# LEDBatterychargeIndicatorCircuitV2.net
KiCad netlist of a schematic drawn in EAGLE
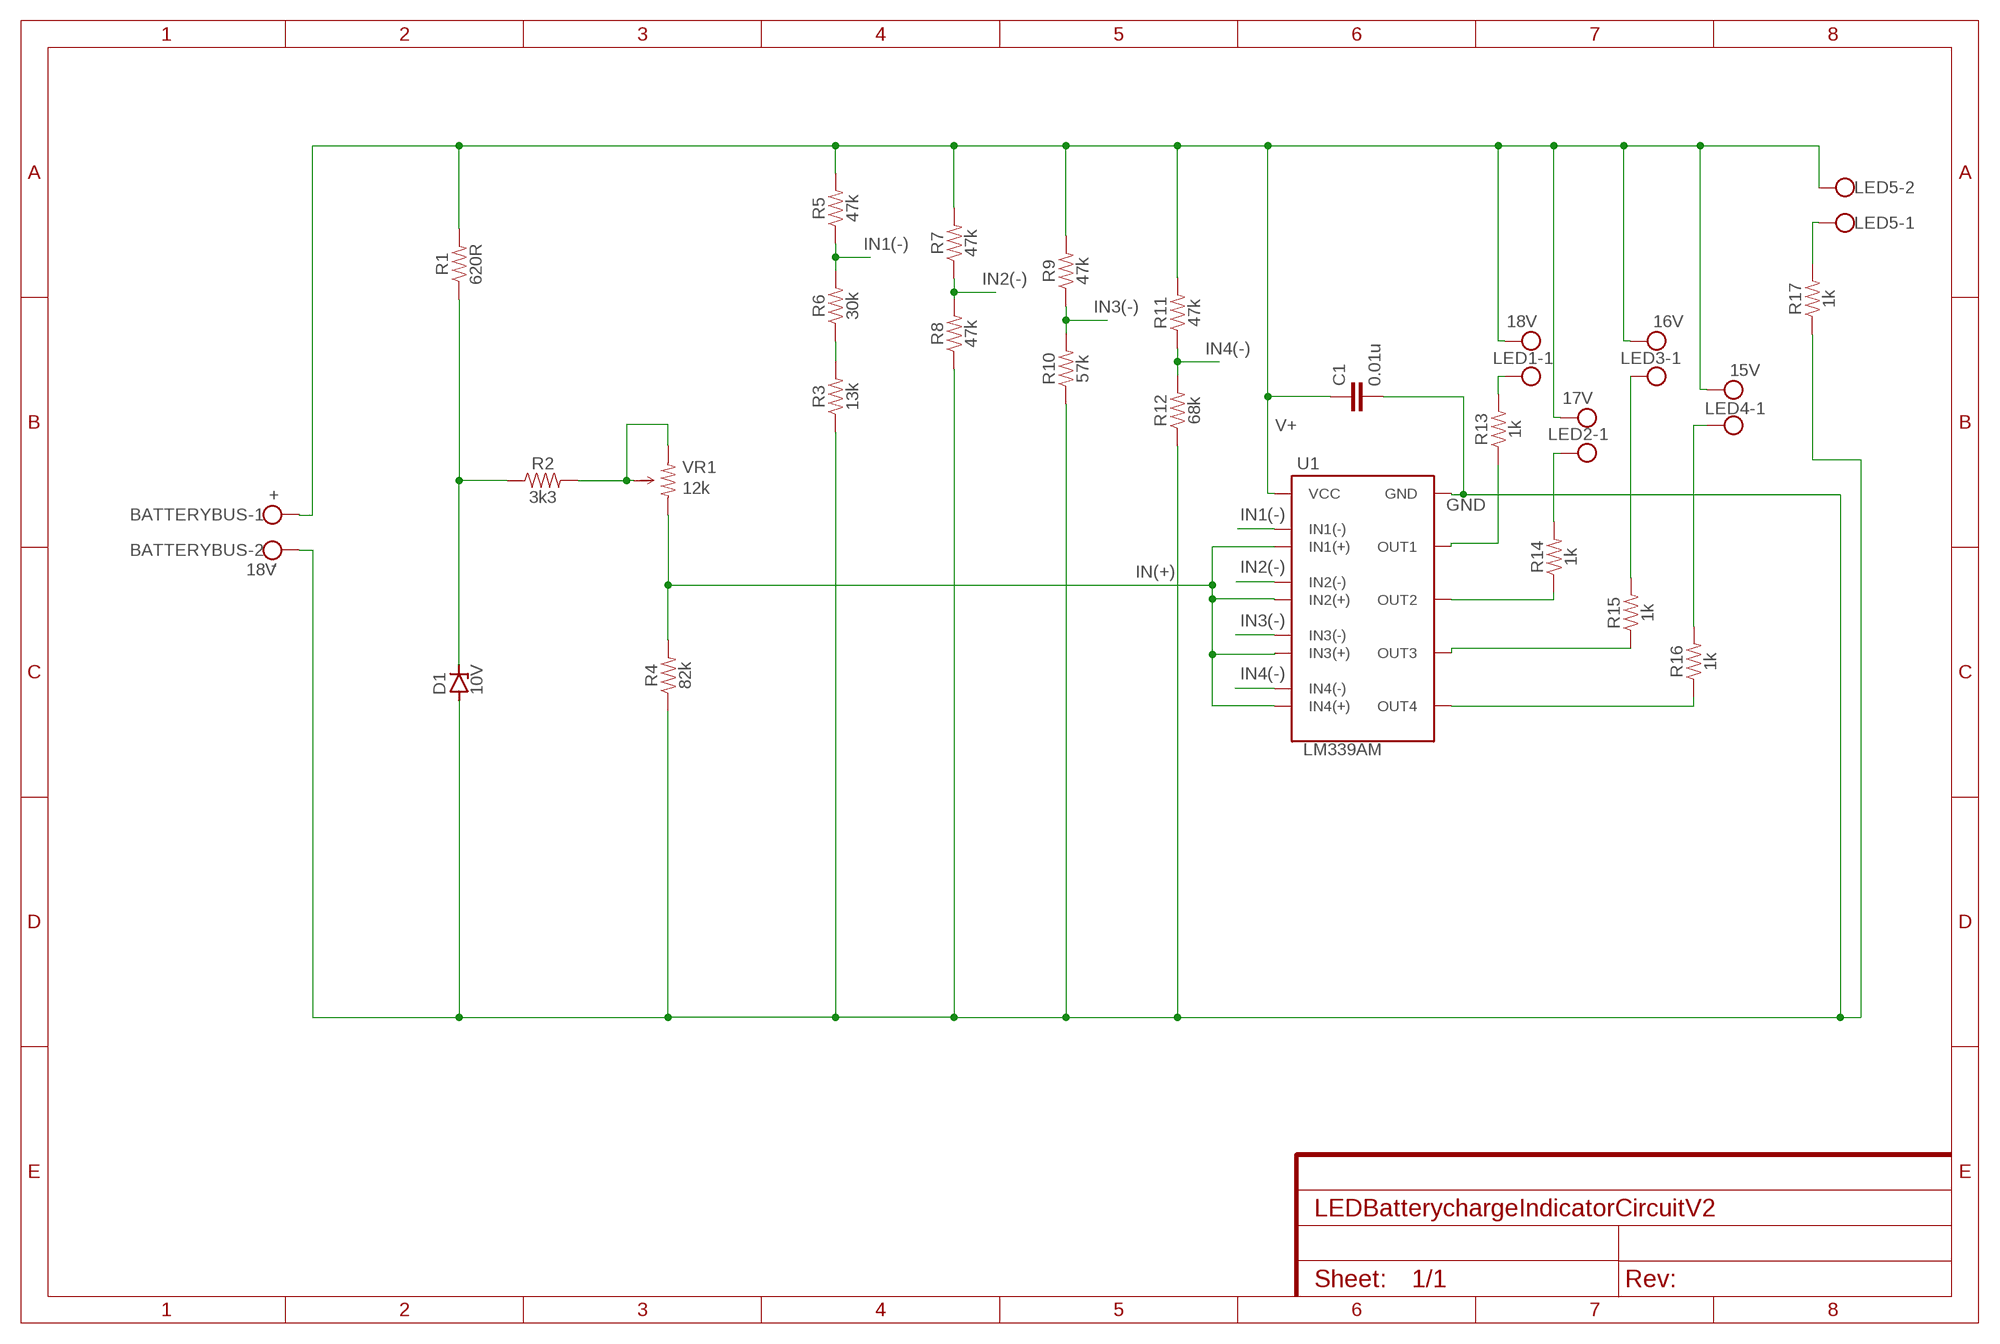
[diagram p0: schematic, sheet 1]

(export (version "E")
  (design (tool "Eeschema 10.0.6"))
  (components
    (comp (ref "BATTERYBUS")
      (value "18V")
      (footprint "eagle-import:W237-102")
      (fields (field (name "MPN") "237-102"))
      (libsource (lib "eagle-import") (part "W237-102"))
    )
    (comp (ref "C1")
      (value "0.01u")
      (footprint "eagle-import:0805")
      (libsource (lib "eagle-import") (part "0.33UF/330NF-0805-50V-10%"))
    )
    (comp (ref "D1")
      (value "10V")
      (footprint "eagle-import:SOT23")
      (libsource (lib "eagle-import") (part "ZENER-DIODESOT23"))
    )
    (comp (ref "LED1")
      (value "18V")
      (footprint "eagle-import:W237-102")
      (fields (field (name "MPN") "237-102"))
      (libsource (lib "eagle-import") (part "W237-102"))
    )
    (comp (ref "LED2")
      (value "17V")
      (footprint "eagle-import:W237-102")
      (fields (field (name "MPN") "237-102"))
      (libsource (lib "eagle-import") (part "W237-102"))
    )
    (comp (ref "LED3")
      (value "16V")
      (footprint "eagle-import:W237-102")
      (fields (field (name "MPN") "237-102"))
      (libsource (lib "eagle-import") (part "W237-102"))
    )
    (comp (ref "LED4")
      (value "15V")
      (footprint "eagle-import:W237-102")
      (fields (field (name "MPN") "237-102"))
      (libsource (lib "eagle-import") (part "W237-102"))
    )
    (comp (ref "LED5")
      (value "W237-102")
      (footprint "eagle-import:W237-102")
      (fields (field (name "MPN") "237-102"))
      (libsource (lib "eagle-import") (part "W237-102"))
    )
    (comp (ref "R1")
      (value "620R")
      (footprint "eagle-import:0805")
      (libsource (lib "eagle-import") (part "RESISTOR0805"))
    )
    (comp (ref "R2")
      (value "3k3")
      (footprint "eagle-import:0805")
      (libsource (lib "eagle-import") (part "RESISTOR0805"))
    )
    (comp (ref "R3")
      (value "13k")
      (footprint "eagle-import:0805")
      (libsource (lib "eagle-import") (part "RESISTOR0805"))
    )
    (comp (ref "R4")
      (value "82k")
      (footprint "eagle-import:0805")
      (libsource (lib "eagle-import") (part "RESISTOR0805"))
    )
    (comp (ref "R5")
      (value "47k")
      (footprint "eagle-import:0805")
      (libsource (lib "eagle-import") (part "RESISTOR0805"))
    )
    (comp (ref "R6")
      (value "30k")
      (footprint "eagle-import:0805")
      (libsource (lib "eagle-import") (part "RESISTOR0805"))
    )
    (comp (ref "R7")
      (value "47k")
      (footprint "eagle-import:0805")
      (libsource (lib "eagle-import") (part "RESISTOR0805"))
    )
    (comp (ref "R8")
      (value "47k")
      (footprint "eagle-import:0805")
      (libsource (lib "eagle-import") (part "RESISTOR0805"))
    )
    (comp (ref "R9")
      (value "47k")
      (footprint "eagle-import:0805")
      (libsource (lib "eagle-import") (part "RESISTOR0805"))
    )
    (comp (ref "R10")
      (value "57k")
      (footprint "eagle-import:0805")
      (libsource (lib "eagle-import") (part "RESISTOR0805"))
    )
    (comp (ref "R11")
      (value "47k")
      (footprint "eagle-import:0805")
      (libsource (lib "eagle-import") (part "RESISTOR0805"))
    )
    (comp (ref "R12")
      (value "68k")
      (footprint "eagle-import:0805")
      (libsource (lib "eagle-import") (part "RESISTOR0805"))
    )
    (comp (ref "R13")
      (value "1k")
      (footprint "eagle-import:0805")
      (libsource (lib "eagle-import") (part "RESISTOR0805"))
    )
    (comp (ref "R14")
      (value "1k")
      (footprint "eagle-import:0805")
      (libsource (lib "eagle-import") (part "RESISTOR0805"))
    )
    (comp (ref "R15")
      (value "1k")
      (footprint "eagle-import:0805")
      (libsource (lib "eagle-import") (part "RESISTOR0805"))
    )
    (comp (ref "R16")
      (value "1k")
      (footprint "eagle-import:0805")
      (libsource (lib "eagle-import") (part "RESISTOR0805"))
    )
    (comp (ref "R17")
      (value "1k")
      (footprint "eagle-import:0805")
      (libsource (lib "eagle-import") (part "RESISTOR0805"))
    )
    (comp (ref "U1")
      (value "LM339AM")
      (footprint "eagle-import:LM339AM")
      (libsource (lib "eagle-import") (part "LM339AMSMD"))
    )
    (comp (ref "VR1")
      (value "12k")
      (footprint "eagle-import:TRIMPOT3266W")
      (libsource (lib "eagle-import") (part "TRIMPOT3266W"))
    )
  )
  (nets
    (net (code "1") (name "/GND") (class "Default")
      (node (ref "BATTERYBUS") (pin "2") (pinfunction "KL_2") (pintype "passive"))
      (node (ref "C1") (pin "2") (pinfunction "2_2") (pintype "passive"))
      (node (ref "D1") (pin "1") (pinfunction "A_1") (pintype "passive"))
      (node (ref "R10") (pin "1") (pinfunction "1_1") (pintype "passive"))
      (node (ref "R12") (pin "1") (pinfunction "1_1") (pintype "passive"))
      (node (ref "R17") (pin "1") (pinfunction "1_1") (pintype "passive"))
      (node (ref "R3") (pin "1") (pinfunction "1_1") (pintype "passive"))
      (node (ref "R4") (pin "1") (pinfunction "1_1") (pintype "passive"))
      (node (ref "R8") (pin "1") (pinfunction "1_1") (pintype "passive"))
      (node (ref "U1") (pin "12") (pinfunction "GND_12") (pintype "power_in"))
    )
    (net (code "2") (name "/IN(+)") (class "Default")
      (node (ref "R4") (pin "2") (pinfunction "2_2") (pintype "passive"))
      (node (ref "U1") (pin "11") (pinfunction "IN4(+)_11") (pintype "input"))
      (node (ref "U1") (pin "5") (pinfunction "IN1(+)_5") (pintype "input"))
      (node (ref "U1") (pin "7") (pinfunction "IN2(+)_7") (pintype "input"))
      (node (ref "U1") (pin "9") (pinfunction "IN3(+)_9") (pintype "input"))
      (node (ref "VR1") (pin "1") (pinfunction "1_1") (pintype "bidirectional"))
    )
    (net (code "3") (name "/IN1(-)") (class "Default")
      (node (ref "R5") (pin "1") (pinfunction "1_1") (pintype "passive"))
      (node (ref "R6") (pin "2") (pinfunction "2_2") (pintype "passive"))
      (node (ref "U1") (pin "4") (pinfunction "IN1(-)_4") (pintype "input"))
    )
    (net (code "4") (name "/IN2(-)") (class "Default")
      (node (ref "R7") (pin "1") (pinfunction "1_1") (pintype "passive"))
      (node (ref "R8") (pin "2") (pinfunction "2_2") (pintype "passive"))
      (node (ref "U1") (pin "6") (pinfunction "IN2(-)_6") (pintype "input"))
    )
    (net (code "5") (name "/IN3(-)") (class "Default")
      (node (ref "R10") (pin "2") (pinfunction "2_2") (pintype "passive"))
      (node (ref "R9") (pin "1") (pinfunction "1_1") (pintype "passive"))
      (node (ref "U1") (pin "8") (pinfunction "IN3(-)_8") (pintype "input"))
    )
    (net (code "6") (name "/IN4(-)") (class "Default")
      (node (ref "R11") (pin "1") (pinfunction "1_1") (pintype "passive"))
      (node (ref "R12") (pin "2") (pinfunction "2_2") (pintype "passive"))
      (node (ref "U1") (pin "10") (pinfunction "IN4(-)_10") (pintype "input"))
    )
    (net (code "7") (name "/V+") (class "Default")
      (node (ref "BATTERYBUS") (pin "1") (pinfunction "KL_1") (pintype "passive"))
      (node (ref "C1") (pin "1") (pinfunction "1_1") (pintype "passive"))
      (node (ref "LED1") (pin "2") (pinfunction "KL_2") (pintype "passive"))
      (node (ref "LED2") (pin "2") (pinfunction "KL_2") (pintype "passive"))
      (node (ref "LED3") (pin "2") (pinfunction "KL_2") (pintype "passive"))
      (node (ref "LED4") (pin "2") (pinfunction "KL_2") (pintype "passive"))
      (node (ref "LED5") (pin "2") (pinfunction "KL_2") (pintype "passive"))
      (node (ref "R1") (pin "2") (pinfunction "2_2") (pintype "passive"))
      (node (ref "R11") (pin "2") (pinfunction "2_2") (pintype "passive"))
      (node (ref "R5") (pin "2") (pinfunction "2_2") (pintype "passive"))
      (node (ref "R7") (pin "2") (pinfunction "2_2") (pintype "passive"))
      (node (ref "R9") (pin "2") (pinfunction "2_2") (pintype "passive"))
      (node (ref "U1") (pin "3") (pinfunction "VCC_3") (pintype "power_in"))
    )
    (net (code "8") (name "Net-(D1-C)") (class "Default")
      (node (ref "D1") (pin "3") (pinfunction "C_3") (pintype "passive"))
      (node (ref "R1") (pin "1") (pinfunction "1_1") (pintype "passive"))
      (node (ref "R2") (pin "1") (pinfunction "1_1") (pintype "passive"))
    )
    (net (code "9") (name "Net-(LED1A-KL)") (class "Default")
      (node (ref "LED1") (pin "1") (pinfunction "KL_1") (pintype "passive"))
      (node (ref "R13") (pin "2") (pinfunction "2_2") (pintype "passive"))
    )
    (net (code "10") (name "Net-(LED2A-KL)") (class "Default")
      (node (ref "LED2") (pin "1") (pinfunction "KL_1") (pintype "passive"))
      (node (ref "R14") (pin "2") (pinfunction "2_2") (pintype "passive"))
    )
    (net (code "11") (name "Net-(LED3A-KL)") (class "Default")
      (node (ref "LED3") (pin "1") (pinfunction "KL_1") (pintype "passive"))
      (node (ref "R15") (pin "2") (pinfunction "2_2") (pintype "passive"))
    )
    (net (code "12") (name "Net-(LED4A-KL)") (class "Default")
      (node (ref "LED4") (pin "1") (pinfunction "KL_1") (pintype "passive"))
      (node (ref "R16") (pin "2") (pinfunction "2_2") (pintype "passive"))
    )
    (net (code "13") (name "Net-(LED5A-KL)") (class "Default")
      (node (ref "LED5") (pin "1") (pinfunction "KL_1") (pintype "passive"))
      (node (ref "R17") (pin "2") (pinfunction "2_2") (pintype "passive"))
    )
    (net (code "14") (name "Net-(R3-Pad2)") (class "Default")
      (node (ref "R3") (pin "2") (pinfunction "2_2") (pintype "passive"))
      (node (ref "R6") (pin "1") (pinfunction "1_1") (pintype "passive"))
    )
    (net (code "15") (name "Net-(U1-OUT1)") (class "Default")
      (node (ref "R13") (pin "1") (pinfunction "1_1") (pintype "passive"))
      (node (ref "U1") (pin "2") (pinfunction "OUT1_2") (pintype "output"))
    )
    (net (code "16") (name "Net-(U1-OUT2)") (class "Default")
      (node (ref "R14") (pin "1") (pinfunction "1_1") (pintype "passive"))
      (node (ref "U1") (pin "1") (pinfunction "OUT2_1") (pintype "output"))
    )
    (net (code "17") (name "Net-(U1-OUT3)") (class "Default")
      (node (ref "R15") (pin "1") (pinfunction "1_1") (pintype "passive"))
      (node (ref "U1") (pin "14") (pinfunction "OUT3_14") (pintype "output"))
    )
    (net (code "18") (name "Net-(U1-OUT4)") (class "Default")
      (node (ref "R16") (pin "1") (pinfunction "1_1") (pintype "passive"))
      (node (ref "U1") (pin "13") (pinfunction "OUT4_13") (pintype "output"))
    )
    (net (code "19") (name "Net-(VR1-WIPER)") (class "Default")
      (node (ref "R2") (pin "2") (pinfunction "2_2") (pintype "passive"))
      (node (ref "VR1") (pin "2") (pinfunction "WIPER_2") (pintype "bidirectional"))
      (node (ref "VR1") (pin "3") (pinfunction "3_3") (pintype "bidirectional"))
    )
  )
)
